# Cube4Control.net
KiCad netlist of a schematic drawn in EAGLE
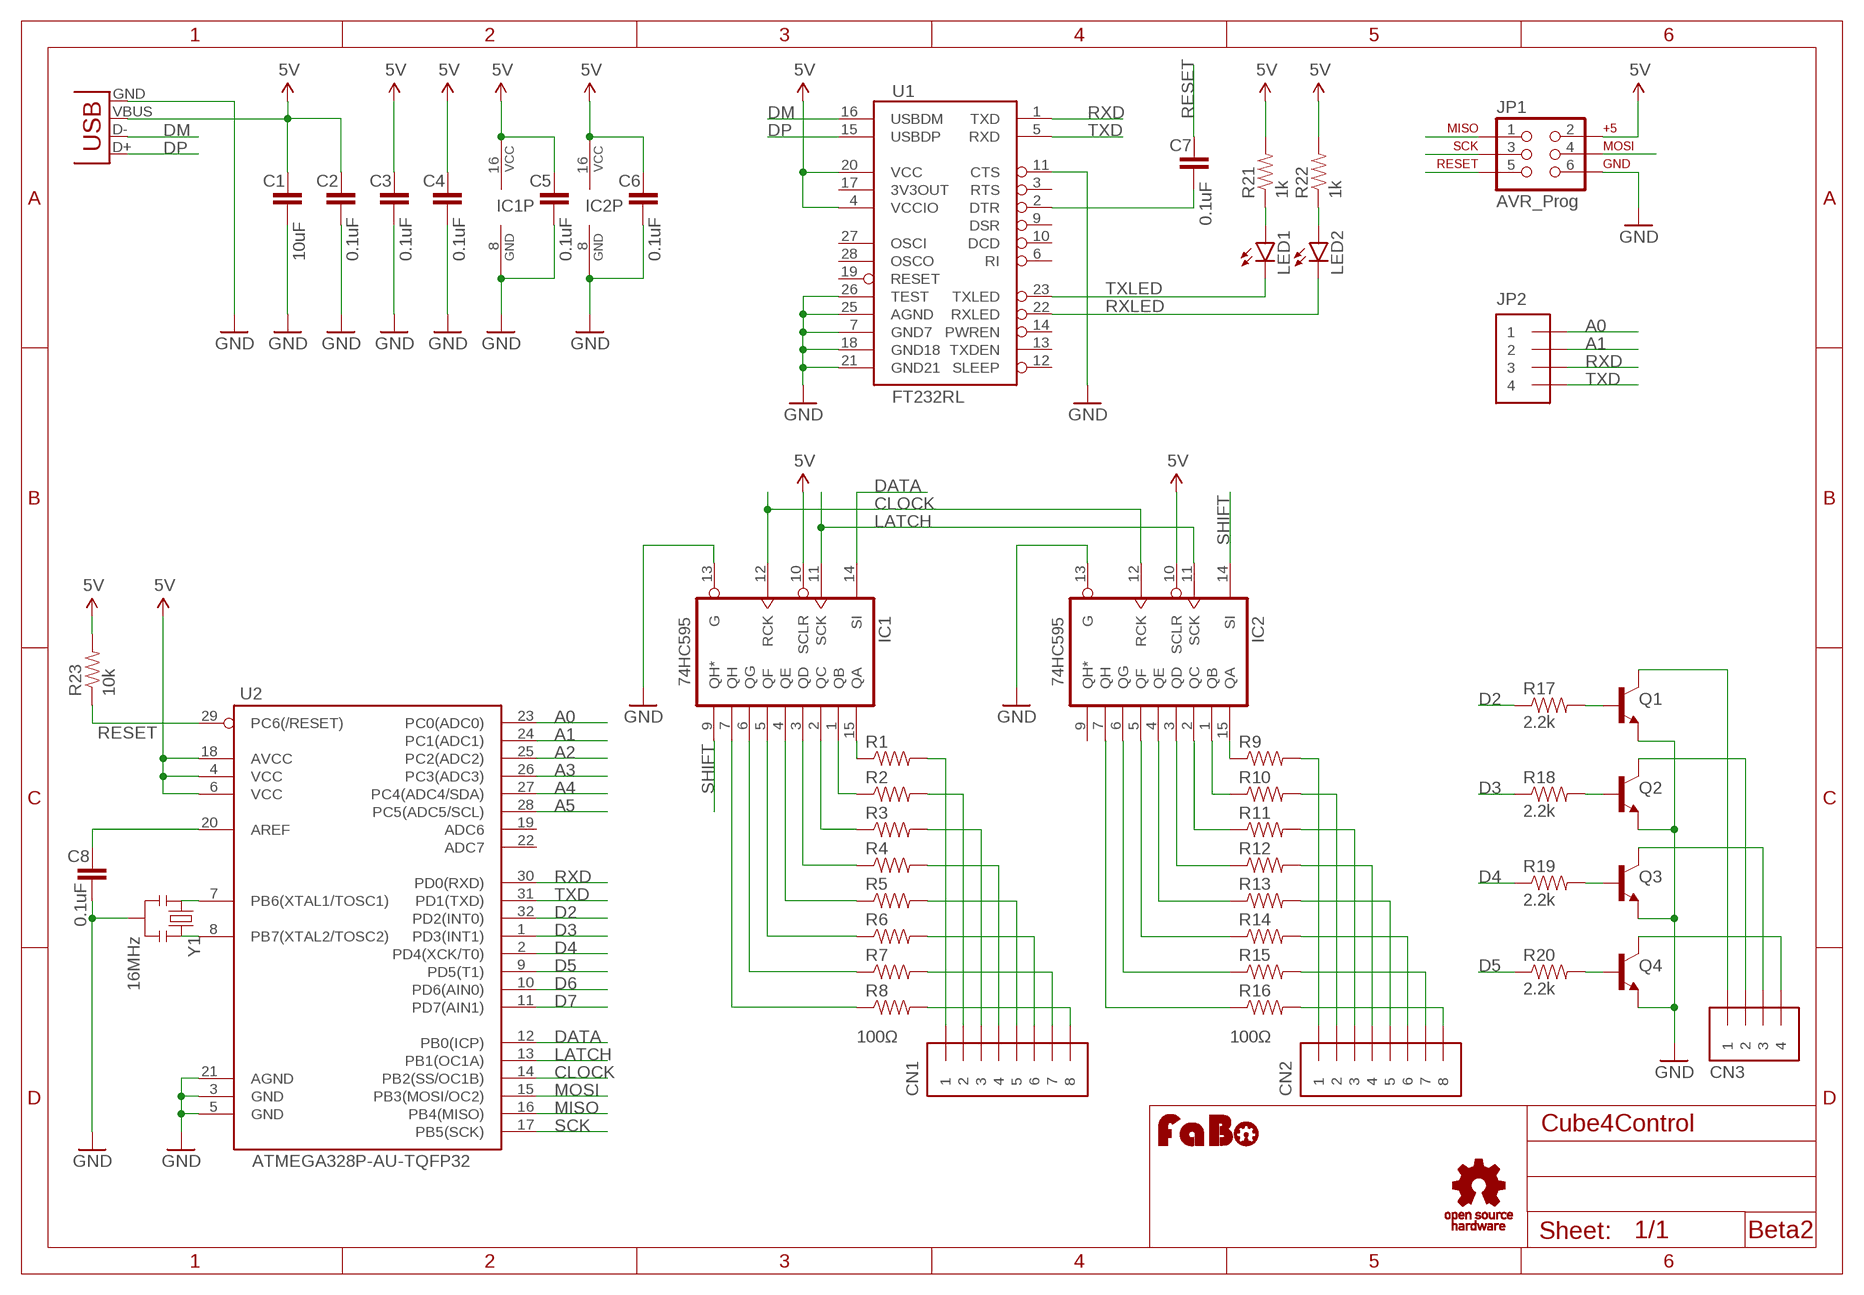
[diagram p0: schematic, sheet 1]

(export (version "E")
  (design (tool "Eeschema 10.0.6"))
  (components
    (comp (ref "C1")
      (value "10uF")
      (footprint "eagle-import:EIA1206")
      (libsource (lib "eagle-import") (part "CAP-EIA1206"))
    )
    (comp (ref "C2")
      (value "0.1uF")
      (footprint "eagle-import:EIA0603")
      (libsource (lib "eagle-import") (part "CAP-EIA0603"))
    )
    (comp (ref "C3")
      (value "0.1uF")
      (footprint "eagle-import:EIA0603")
      (libsource (lib "eagle-import") (part "CAP-EIA0603"))
    )
    (comp (ref "C4")
      (value "0.1uF")
      (footprint "eagle-import:EIA0603")
      (libsource (lib "eagle-import") (part "CAP-EIA0603"))
    )
    (comp (ref "C5")
      (value "0.1uF")
      (footprint "eagle-import:EIA0603")
      (libsource (lib "eagle-import") (part "CAP-EIA0603"))
    )
    (comp (ref "C6")
      (value "0.1uF")
      (footprint "eagle-import:EIA0603")
      (libsource (lib "eagle-import") (part "CAP-EIA0603"))
    )
    (comp (ref "C7")
      (value "0.1uF")
      (footprint "eagle-import:EIA0603")
      (libsource (lib "eagle-import") (part "CAP-EIA0603"))
    )
    (comp (ref "C8")
      (value "0.1uF")
      (footprint "eagle-import:EIA0603")
      (libsource (lib "eagle-import") (part "CAP-EIA0603"))
    )
    (comp (ref "CN1")
      (value "PINHEAD-1X8")
      (footprint "eagle-import:1X8-SNEAKY")
      (libsource (lib "eagle-import") (part "PINHEAD-1X8"))
    )
    (comp (ref "CN2")
      (value "PINHEAD-1X8")
      (footprint "eagle-import:1X8-SNEAKY")
      (libsource (lib "eagle-import") (part "PINHEAD-1X8"))
    )
    (comp (ref "CN3")
      (value "PINHEAD-1X4")
      (footprint "eagle-import:1X4-SNEAKY")
      (libsource (lib "eagle-import") (part "PINHEAD-1X4"))
    )
    (comp (ref "IC1")
      (value "74HC595")
      (footprint "eagle-import:SO16-3.9")
      (libsource (lib "eagle-import") (part "74HC595-SO16"))
    )
    (comp (ref "IC2")
      (value "74HC595")
      (footprint "eagle-import:SO16-3.9")
      (libsource (lib "eagle-import") (part "74HC595-SO16"))
    )
    (comp (ref "JP1")
      (value "AVR_Prog")
      (footprint "eagle-import:TC2030-MCP")
      (libsource (lib "eagle-import") (part "AVR_ISP-TC"))
    )
    (comp (ref "JP2")
      (value "PINHEAD-1X4")
      (footprint "eagle-import:1X4-SNEAKY")
      (libsource (lib "eagle-import") (part "PINHEAD-1X4"))
    )
    (comp (ref "LED1")
      (value "LED-EIA0603")
      (footprint "eagle-import:EIA0603-LED")
      (libsource (lib "eagle-import") (part "LED-EIA0603"))
    )
    (comp (ref "LED2")
      (value "LED-EIA0603")
      (footprint "eagle-import:EIA0603-LED")
      (libsource (lib "eagle-import") (part "LED-EIA0603"))
    )
    (comp (ref "Q1")
      (value "NPN-2SC3325")
      (footprint "eagle-import:SOT23-3")
      (libsource (lib "eagle-import") (part "NPN-2SC3325"))
    )
    (comp (ref "Q2")
      (value "NPN-2SC3325")
      (footprint "eagle-import:SOT23-3")
      (libsource (lib "eagle-import") (part "NPN-2SC3325"))
    )
    (comp (ref "Q3")
      (value "NPN-2SC3325")
      (footprint "eagle-import:SOT23-3")
      (libsource (lib "eagle-import") (part "NPN-2SC3325"))
    )
    (comp (ref "Q4")
      (value "NPN-2SC3325")
      (footprint "eagle-import:SOT23-3")
      (libsource (lib "eagle-import") (part "NPN-2SC3325"))
    )
    (comp (ref "R1")
      (value "RES-EIA0603")
      (footprint "eagle-import:EIA0603@1")
      (libsource (lib "eagle-import") (part "RES-EIA0603"))
    )
    (comp (ref "R2")
      (value "RES-EIA0603")
      (footprint "eagle-import:EIA0603@1")
      (libsource (lib "eagle-import") (part "RES-EIA0603"))
    )
    (comp (ref "R3")
      (value "RES-EIA0603")
      (footprint "eagle-import:EIA0603@1")
      (libsource (lib "eagle-import") (part "RES-EIA0603"))
    )
    (comp (ref "R4")
      (value "RES-EIA0603")
      (footprint "eagle-import:EIA0603@1")
      (libsource (lib "eagle-import") (part "RES-EIA0603"))
    )
    (comp (ref "R5")
      (value "RES-EIA0603")
      (footprint "eagle-import:EIA0603@1")
      (libsource (lib "eagle-import") (part "RES-EIA0603"))
    )
    (comp (ref "R6")
      (value "RES-EIA0603")
      (footprint "eagle-import:EIA0603@1")
      (libsource (lib "eagle-import") (part "RES-EIA0603"))
    )
    (comp (ref "R7")
      (value "RES-EIA0603")
      (footprint "eagle-import:EIA0603@1")
      (libsource (lib "eagle-import") (part "RES-EIA0603"))
    )
    (comp (ref "R8")
      (value "RES-EIA0603")
      (footprint "eagle-import:EIA0603@1")
      (libsource (lib "eagle-import") (part "RES-EIA0603"))
    )
    (comp (ref "R9")
      (value "RES-EIA0603")
      (footprint "eagle-import:EIA0603@1")
      (libsource (lib "eagle-import") (part "RES-EIA0603"))
    )
    (comp (ref "R10")
      (value "RES-EIA0603")
      (footprint "eagle-import:EIA0603@1")
      (libsource (lib "eagle-import") (part "RES-EIA0603"))
    )
    (comp (ref "R11")
      (value "RES-EIA0603")
      (footprint "eagle-import:EIA0603@1")
      (libsource (lib "eagle-import") (part "RES-EIA0603"))
    )
    (comp (ref "R12")
      (value "RES-EIA0603")
      (footprint "eagle-import:EIA0603@1")
      (libsource (lib "eagle-import") (part "RES-EIA0603"))
    )
    (comp (ref "R13")
      (value "RES-EIA0603")
      (footprint "eagle-import:EIA0603@1")
      (libsource (lib "eagle-import") (part "RES-EIA0603"))
    )
    (comp (ref "R14")
      (value "RES-EIA0603")
      (footprint "eagle-import:EIA0603@1")
      (libsource (lib "eagle-import") (part "RES-EIA0603"))
    )
    (comp (ref "R15")
      (value "RES-EIA0603")
      (footprint "eagle-import:EIA0603@1")
      (libsource (lib "eagle-import") (part "RES-EIA0603"))
    )
    (comp (ref "R16")
      (value "RES-EIA0603")
      (footprint "eagle-import:EIA0603@1")
      (libsource (lib "eagle-import") (part "RES-EIA0603"))
    )
    (comp (ref "R17")
      (value "2.2k")
      (footprint "eagle-import:EIA0603@1")
      (libsource (lib "eagle-import") (part "RES-EIA0603"))
    )
    (comp (ref "R18")
      (value "2.2k")
      (footprint "eagle-import:EIA0603@1")
      (libsource (lib "eagle-import") (part "RES-EIA0603"))
    )
    (comp (ref "R19")
      (value "2.2k")
      (footprint "eagle-import:EIA0603@1")
      (libsource (lib "eagle-import") (part "RES-EIA0603"))
    )
    (comp (ref "R20")
      (value "2.2k")
      (footprint "eagle-import:EIA0603@1")
      (libsource (lib "eagle-import") (part "RES-EIA0603"))
    )
    (comp (ref "R21")
      (value "1k")
      (footprint "eagle-import:EIA0603@1")
      (libsource (lib "eagle-import") (part "RES-EIA0603"))
    )
    (comp (ref "R22")
      (value "1k")
      (footprint "eagle-import:EIA0603@1")
      (libsource (lib "eagle-import") (part "RES-EIA0603"))
    )
    (comp (ref "R23")
      (value "10k")
      (footprint "eagle-import:EIA0603@1")
      (libsource (lib "eagle-import") (part "RES-EIA0603"))
    )
    (comp (ref "U$2")
      (value "LOGO_FABO-M")
      (footprint "eagle-import:LOGO_FABO_M")
      (libsource (lib "eagle-import") (part "LOGO_FABO-M"))
    )
    (comp (ref "U$4")
      (value "LOGO_OSHW_T-M")
      (footprint "eagle-import:LOGO_OSHW_T_M")
      (libsource (lib "eagle-import") (part "LOGO_OSHW_T-M"))
    )
    (comp (ref "U1")
      (value "FT232RL")
      (footprint "eagle-import:SSOP28")
      (libsource (lib "eagle-import") (part "FT232RL"))
    )
    (comp (ref "U2")
      (value "ATMEGA328P-AU-TQFP32")
      (footprint "eagle-import:TQFP-32-08")
      (libsource (lib "eagle-import") (part "ATMEGA328P-AU-TQFP32"))
    )
    (comp (ref "USB1")
      (value "USB-B-MICRO_SMD")
      (footprint "eagle-import:USB_B_MICRO")
      (libsource (lib "eagle-import") (part "USB-B-MICRO_SMD"))
    )
    (comp (ref "Y1")
      (value "16MHz")
      (footprint "eagle-import:RESONATOR_SMD")
      (libsource (lib "eagle-import") (part "RESONATOR"))
    )
  )
  (nets
    (net (code "1") (name "/A0") (class "Default")
      (node (ref "JP2") (pin "1") (pinfunction "1_1") (pintype "bidirectional"))
      (node (ref "U2") (pin "23") (pinfunction "PC0(ADC0)_23") (pintype "bidirectional"))
    )
    (net (code "2") (name "/A1") (class "Default")
      (node (ref "JP2") (pin "2") (pinfunction "2_2") (pintype "bidirectional"))
      (node (ref "U2") (pin "24") (pinfunction "PC1(ADC1)_24") (pintype "bidirectional"))
    )
    (net (code "3") (name "/A2") (class "Default")
      (node (ref "U2") (pin "25") (pinfunction "PC2(ADC2)_25") (pintype "bidirectional"))
    )
    (net (code "4") (name "/A3") (class "Default")
      (node (ref "U2") (pin "26") (pinfunction "PC3(ADC3)_26") (pintype "bidirectional"))
    )
    (net (code "5") (name "/A4") (class "Default")
      (node (ref "U2") (pin "27") (pinfunction "PC4(ADC4/SDA)_27") (pintype "bidirectional"))
    )
    (net (code "6") (name "/A5") (class "Default")
      (node (ref "U2") (pin "28") (pinfunction "PC5(ADC5/SCL)_28") (pintype "bidirectional"))
    )
    (net (code "7") (name "/CLOCK") (class "Default")
      (node (ref "IC1") (pin "12") (pinfunction "RCK_12") (pintype "input"))
      (node (ref "IC2") (pin "12") (pinfunction "RCK_12") (pintype "input"))
      (node (ref "U2") (pin "14") (pinfunction "PB2(SS/OC1B)_14") (pintype "bidirectional"))
    )
    (net (code "8") (name "/D2") (class "Default")
      (node (ref "R17") (pin "1") (pinfunction "1_1") (pintype "passive"))
      (node (ref "U2") (pin "32") (pinfunction "PD2(INT0)_32") (pintype "bidirectional"))
    )
    (net (code "9") (name "/D3") (class "Default")
      (node (ref "R18") (pin "1") (pinfunction "1_1") (pintype "passive"))
      (node (ref "U2") (pin "1") (pinfunction "PD3(INT1)_1") (pintype "bidirectional"))
    )
    (net (code "10") (name "/D4") (class "Default")
      (node (ref "R19") (pin "1") (pinfunction "1_1") (pintype "passive"))
      (node (ref "U2") (pin "2") (pinfunction "PD4(XCK/T0)_2") (pintype "bidirectional"))
    )
    (net (code "11") (name "/D5") (class "Default")
      (node (ref "R20") (pin "1") (pinfunction "1_1") (pintype "passive"))
      (node (ref "U2") (pin "9") (pinfunction "PD5(T1)_9") (pintype "bidirectional"))
    )
    (net (code "12") (name "/D6") (class "Default")
      (node (ref "U2") (pin "10") (pinfunction "PD6(AIN0)_10") (pintype "bidirectional"))
    )
    (net (code "13") (name "/D7") (class "Default")
      (node (ref "U2") (pin "11") (pinfunction "PD7(AIN1)_11") (pintype "bidirectional"))
    )
    (net (code "14") (name "/DATA") (class "Default")
      (node (ref "IC1") (pin "14") (pinfunction "SI_14") (pintype "input"))
      (node (ref "U2") (pin "12") (pinfunction "PB0(ICP)_12") (pintype "bidirectional"))
    )
    (net (code "15") (name "/DM") (class "Default")
      (node (ref "U1") (pin "16") (pinfunction "USBDM_16") (pintype "bidirectional"))
      (node (ref "USB1") (pin "D-") (pinfunction "D-_D-") (pintype "bidirectional"))
    )
    (net (code "16") (name "/DP") (class "Default")
      (node (ref "U1") (pin "15") (pinfunction "USBDP_15") (pintype "bidirectional"))
      (node (ref "USB1") (pin "D+") (pinfunction "D+_D+") (pintype "bidirectional"))
    )
    (net (code "17") (name "/LATCH") (class "Default")
      (node (ref "IC1") (pin "11") (pinfunction "SCK_11") (pintype "input"))
      (node (ref "IC2") (pin "11") (pinfunction "SCK_11") (pintype "input"))
      (node (ref "U2") (pin "13") (pinfunction "PB1(OC1A)_13") (pintype "bidirectional"))
    )
    (net (code "18") (name "/MISO") (class "Default")
      (node (ref "JP1") (pin "1") (pinfunction "1_1") (pintype "passive"))
      (node (ref "U2") (pin "16") (pinfunction "PB4(MISO)_16") (pintype "bidirectional"))
    )
    (net (code "19") (name "/MOSI") (class "Default")
      (node (ref "JP1") (pin "4") (pinfunction "4_4") (pintype "passive"))
      (node (ref "U2") (pin "15") (pinfunction "PB3(MOSI/OC2)_15") (pintype "bidirectional"))
    )
    (net (code "20") (name "/RESET") (class "Default")
      (node (ref "C7") (pin "1") (pinfunction "1_1") (pintype "passive"))
      (node (ref "JP1") (pin "5") (pinfunction "5_5") (pintype "passive"))
      (node (ref "R23") (pin "1") (pinfunction "1_1") (pintype "passive"))
      (node (ref "U2") (pin "29") (pinfunction "PC6(/RESET)_29") (pintype "bidirectional"))
    )
    (net (code "21") (name "/RXD") (class "Default")
      (node (ref "JP2") (pin "3") (pinfunction "3_3") (pintype "bidirectional"))
      (node (ref "U1") (pin "1") (pinfunction "TXD_1") (pintype "output"))
      (node (ref "U2") (pin "30") (pinfunction "PD0(RXD)_30") (pintype "bidirectional"))
    )
    (net (code "22") (name "/RXLED") (class "Default")
      (node (ref "LED2") (pin "C") (pinfunction "C_C") (pintype "passive"))
      (node (ref "U1") (pin "22") (pinfunction "RXLED_22") (pintype "input"))
    )
    (net (code "23") (name "/SCK") (class "Default")
      (node (ref "JP1") (pin "3") (pinfunction "3_3") (pintype "passive"))
      (node (ref "U2") (pin "17") (pinfunction "PB5(SCK)_17") (pintype "bidirectional"))
    )
    (net (code "24") (name "/SHIFT") (class "Default")
      (node (ref "IC1") (pin "9") (pinfunction "QH*_9") (pintype "tri_state"))
      (node (ref "IC2") (pin "14") (pinfunction "SI_14") (pintype "input"))
    )
    (net (code "25") (name "/TXD") (class "Default")
      (node (ref "JP2") (pin "4") (pinfunction "4_4") (pintype "bidirectional"))
      (node (ref "U1") (pin "5") (pinfunction "RXD_5") (pintype "input"))
      (node (ref "U2") (pin "31") (pinfunction "PD1(TXD)_31") (pintype "bidirectional"))
    )
    (net (code "26") (name "/TXLED") (class "Default")
      (node (ref "LED1") (pin "C") (pinfunction "C_C") (pintype "passive"))
      (node (ref "U1") (pin "23") (pinfunction "TXLED_23") (pintype "input"))
    )
    (net (code "27") (name "5V") (class "Default")
      (node (ref "C1") (pin "1") (pinfunction "1_1") (pintype "passive"))
      (node (ref "C2") (pin "1") (pinfunction "1_1") (pintype "passive"))
      (node (ref "C3") (pin "1") (pinfunction "1_1") (pintype "passive"))
      (node (ref "C4") (pin "1") (pinfunction "1_1") (pintype "passive"))
      (node (ref "C5") (pin "1") (pinfunction "1_1") (pintype "passive"))
      (node (ref "C6") (pin "1") (pinfunction "1_1") (pintype "passive"))
      (node (ref "IC1") (pin "10") (pinfunction "SCLR_10") (pintype "input"))
      (node (ref "IC1") (pin "16") (pinfunction "VCC_16") (pintype "power_in"))
      (node (ref "IC2") (pin "10") (pinfunction "SCLR_10") (pintype "input"))
      (node (ref "IC2") (pin "16") (pinfunction "VCC_16") (pintype "power_in"))
      (node (ref "JP1") (pin "2") (pinfunction "2_2") (pintype "passive"))
      (node (ref "R21") (pin "2") (pinfunction "2_2") (pintype "passive"))
      (node (ref "R22") (pin "2") (pinfunction "2_2") (pintype "passive"))
      (node (ref "R23") (pin "2") (pinfunction "2_2") (pintype "passive"))
      (node (ref "U1") (pin "20") (pinfunction "VCC_20") (pintype "power_in"))
      (node (ref "U1") (pin "4") (pinfunction "VCCIO_4") (pintype "power_in"))
      (node (ref "U2") (pin "18") (pinfunction "AVCC_18") (pintype "bidirectional"))
      (node (ref "U2") (pin "4") (pinfunction "VCC_4") (pintype "bidirectional"))
      (node (ref "U2") (pin "6") (pinfunction "VCC_6") (pintype "bidirectional"))
      (node (ref "USB1") (pin "VBUS") (pinfunction "VBUS_VBUS") (pintype "bidirectional"))
    )
    (net (code "28") (name "GND") (class "Default")
      (node (ref "C1") (pin "2") (pinfunction "2_2") (pintype "passive"))
      (node (ref "C2") (pin "2") (pinfunction "2_2") (pintype "passive"))
      (node (ref "C3") (pin "2") (pinfunction "2_2") (pintype "passive"))
      (node (ref "C4") (pin "2") (pinfunction "2_2") (pintype "passive"))
      (node (ref "C5") (pin "2") (pinfunction "2_2") (pintype "passive"))
      (node (ref "C6") (pin "2") (pinfunction "2_2") (pintype "passive"))
      (node (ref "C8") (pin "2") (pinfunction "2_2") (pintype "passive"))
      (node (ref "IC1") (pin "13") (pinfunction "G_13") (pintype "input"))
      (node (ref "IC1") (pin "8") (pinfunction "GND_8") (pintype "power_in"))
      (node (ref "IC2") (pin "13") (pinfunction "G_13") (pintype "input"))
      (node (ref "IC2") (pin "8") (pinfunction "GND_8") (pintype "power_in"))
      (node (ref "JP1") (pin "6") (pinfunction "6_6") (pintype "passive"))
      (node (ref "Q1") (pin "2") (pinfunction "E_2") (pintype "passive"))
      (node (ref "Q2") (pin "2") (pinfunction "E_2") (pintype "passive"))
      (node (ref "Q3") (pin "2") (pinfunction "E_2") (pintype "passive"))
      (node (ref "Q4") (pin "2") (pinfunction "E_2") (pintype "passive"))
      (node (ref "U1") (pin "11") (pinfunction "CTS_11") (pintype "input"))
      (node (ref "U1") (pin "18") (pinfunction "GND18_18") (pintype "power_in"))
      (node (ref "U1") (pin "21") (pinfunction "GND21_21") (pintype "power_in"))
      (node (ref "U1") (pin "25") (pinfunction "AGND_25") (pintype "power_in"))
      (node (ref "U1") (pin "26") (pinfunction "TEST_26") (pintype "input"))
      (node (ref "U1") (pin "7") (pinfunction "GND7_7") (pintype "power_in"))
      (node (ref "U2") (pin "21") (pinfunction "AGND_21") (pintype "bidirectional"))
      (node (ref "U2") (pin "3") (pinfunction "GND_3") (pintype "bidirectional"))
      (node (ref "U2") (pin "5") (pinfunction "GND_5") (pintype "bidirectional"))
      (node (ref "USB1") (pin "GND") (pinfunction "GND_GND") (pintype "bidirectional"))
      (node (ref "Y1") (pin "2") (pinfunction "2_2") (pintype "passive"))
    )
    (net (code "29") (name "Net-(CN1-Pad1)") (class "Default")
      (node (ref "CN1") (pin "1") (pinfunction "1_1") (pintype "bidirectional"))
      (node (ref "R1") (pin "2") (pinfunction "2_2") (pintype "passive"))
    )
    (net (code "30") (name "Net-(CN1-Pad2)") (class "Default")
      (node (ref "CN1") (pin "2") (pinfunction "2_2") (pintype "bidirectional"))
      (node (ref "R2") (pin "2") (pinfunction "2_2") (pintype "passive"))
    )
    (net (code "31") (name "Net-(CN1-Pad3)") (class "Default")
      (node (ref "CN1") (pin "3") (pinfunction "3_3") (pintype "bidirectional"))
      (node (ref "R3") (pin "2") (pinfunction "2_2") (pintype "passive"))
    )
    (net (code "32") (name "Net-(CN1-Pad4)") (class "Default")
      (node (ref "CN1") (pin "4") (pinfunction "4_4") (pintype "bidirectional"))
      (node (ref "R4") (pin "2") (pinfunction "2_2") (pintype "passive"))
    )
    (net (code "33") (name "Net-(CN1-Pad5)") (class "Default")
      (node (ref "CN1") (pin "5") (pinfunction "5_5") (pintype "bidirectional"))
      (node (ref "R5") (pin "2") (pinfunction "2_2") (pintype "passive"))
    )
    (net (code "34") (name "Net-(CN1-Pad6)") (class "Default")
      (node (ref "CN1") (pin "6") (pinfunction "6_6") (pintype "bidirectional"))
      (node (ref "R6") (pin "2") (pinfunction "2_2") (pintype "passive"))
    )
    (net (code "35") (name "Net-(CN1-Pad7)") (class "Default")
      (node (ref "CN1") (pin "7") (pinfunction "7_7") (pintype "bidirectional"))
      (node (ref "R7") (pin "2") (pinfunction "2_2") (pintype "passive"))
    )
    (net (code "36") (name "Net-(CN1-Pad8)") (class "Default")
      (node (ref "CN1") (pin "8") (pinfunction "8_8") (pintype "bidirectional"))
      (node (ref "R8") (pin "2") (pinfunction "2_2") (pintype "passive"))
    )
    (net (code "37") (name "Net-(CN2-Pad1)") (class "Default")
      (node (ref "CN2") (pin "1") (pinfunction "1_1") (pintype "bidirectional"))
      (node (ref "R9") (pin "2") (pinfunction "2_2") (pintype "passive"))
    )
    (net (code "38") (name "Net-(CN2-Pad2)") (class "Default")
      (node (ref "CN2") (pin "2") (pinfunction "2_2") (pintype "bidirectional"))
      (node (ref "R10") (pin "2") (pinfunction "2_2") (pintype "passive"))
    )
    (net (code "39") (name "Net-(CN2-Pad3)") (class "Default")
      (node (ref "CN2") (pin "3") (pinfunction "3_3") (pintype "bidirectional"))
      (node (ref "R11") (pin "2") (pinfunction "2_2") (pintype "passive"))
    )
    (net (code "40") (name "Net-(CN2-Pad4)") (class "Default")
      (node (ref "CN2") (pin "4") (pinfunction "4_4") (pintype "bidirectional"))
      (node (ref "R12") (pin "2") (pinfunction "2_2") (pintype "passive"))
    )
    (net (code "41") (name "Net-(CN2-Pad5)") (class "Default")
      (node (ref "CN2") (pin "5") (pinfunction "5_5") (pintype "bidirectional"))
      (node (ref "R13") (pin "2") (pinfunction "2_2") (pintype "passive"))
    )
    (net (code "42") (name "Net-(CN2-Pad6)") (class "Default")
      (node (ref "CN2") (pin "6") (pinfunction "6_6") (pintype "bidirectional"))
      (node (ref "R14") (pin "2") (pinfunction "2_2") (pintype "passive"))
    )
    (net (code "43") (name "Net-(CN2-Pad7)") (class "Default")
      (node (ref "CN2") (pin "7") (pinfunction "7_7") (pintype "bidirectional"))
      (node (ref "R15") (pin "2") (pinfunction "2_2") (pintype "passive"))
    )
    (net (code "44") (name "Net-(CN2-Pad8)") (class "Default")
      (node (ref "CN2") (pin "8") (pinfunction "8_8") (pintype "bidirectional"))
      (node (ref "R16") (pin "2") (pinfunction "2_2") (pintype "passive"))
    )
    (net (code "45") (name "Net-(IC1A-QA)") (class "Default")
      (node (ref "IC1") (pin "15") (pinfunction "QA_15") (pintype "tri_state"))
      (node (ref "R1") (pin "1") (pinfunction "1_1") (pintype "passive"))
    )
    (net (code "46") (name "Net-(IC1A-QB)") (class "Default")
      (node (ref "IC1") (pin "1") (pinfunction "QB_1") (pintype "tri_state"))
      (node (ref "R2") (pin "1") (pinfunction "1_1") (pintype "passive"))
    )
    (net (code "47") (name "Net-(IC1A-QC)") (class "Default")
      (node (ref "IC1") (pin "2") (pinfunction "QC_2") (pintype "tri_state"))
      (node (ref "R3") (pin "1") (pinfunction "1_1") (pintype "passive"))
    )
    (net (code "48") (name "Net-(IC1A-QD)") (class "Default")
      (node (ref "IC1") (pin "3") (pinfunction "QD_3") (pintype "tri_state"))
      (node (ref "R4") (pin "1") (pinfunction "1_1") (pintype "passive"))
    )
    (net (code "49") (name "Net-(IC1A-QE)") (class "Default")
      (node (ref "IC1") (pin "4") (pinfunction "QE_4") (pintype "tri_state"))
      (node (ref "R5") (pin "1") (pinfunction "1_1") (pintype "passive"))
    )
    (net (code "50") (name "Net-(IC1A-QF)") (class "Default")
      (node (ref "IC1") (pin "5") (pinfunction "QF_5") (pintype "tri_state"))
      (node (ref "R6") (pin "1") (pinfunction "1_1") (pintype "passive"))
    )
    (net (code "51") (name "Net-(IC1A-QG)") (class "Default")
      (node (ref "IC1") (pin "6") (pinfunction "QG_6") (pintype "tri_state"))
      (node (ref "R7") (pin "1") (pinfunction "1_1") (pintype "passive"))
    )
    (net (code "52") (name "Net-(IC1A-QH)") (class "Default")
      (node (ref "IC1") (pin "7") (pinfunction "QH_7") (pintype "tri_state"))
      (node (ref "R8") (pin "1") (pinfunction "1_1") (pintype "passive"))
    )
    (net (code "53") (name "Net-(IC2A-QA)") (class "Default")
      (node (ref "IC2") (pin "15") (pinfunction "QA_15") (pintype "tri_state"))
      (node (ref "R9") (pin "1") (pinfunction "1_1") (pintype "passive"))
    )
    (net (code "54") (name "Net-(IC2A-QB)") (class "Default")
      (node (ref "IC2") (pin "1") (pinfunction "QB_1") (pintype "tri_state"))
      (node (ref "R10") (pin "1") (pinfunction "1_1") (pintype "passive"))
    )
    (net (code "55") (name "Net-(IC2A-QC)") (class "Default")
      (node (ref "IC2") (pin "2") (pinfunction "QC_2") (pintype "tri_state"))
      (node (ref "R11") (pin "1") (pinfunction "1_1") (pintype "passive"))
    )
    (net (code "56") (name "Net-(IC2A-QD)") (class "Default")
      (node (ref "IC2") (pin "3") (pinfunction "QD_3") (pintype "tri_state"))
      (node (ref "R12") (pin "1") (pinfunction "1_1") (pintype "passive"))
    )
    (net (code "57") (name "Net-(IC2A-QE)") (class "Default")
      (node (ref "IC2") (pin "4") (pinfunction "QE_4") (pintype "tri_state"))
      (node (ref "R13") (pin "1") (pinfunction "1_1") (pintype "passive"))
    )
    (net (code "58") (name "Net-(IC2A-QF)") (class "Default")
      (node (ref "IC2") (pin "5") (pinfunction "QF_5") (pintype "tri_state"))
      (node (ref "R14") (pin "1") (pinfunction "1_1") (pintype "passive"))
    )
    (net (code "59") (name "Net-(IC2A-QG)") (class "Default")
      (node (ref "IC2") (pin "6") (pinfunction "QG_6") (pintype "tri_state"))
      (node (ref "R15") (pin "1") (pinfunction "1_1") (pintype "passive"))
    )
    (net (code "60") (name "Net-(IC2A-QH)") (class "Default")
      (node (ref "IC2") (pin "7") (pinfunction "QH_7") (pintype "tri_state"))
      (node (ref "R16") (pin "1") (pinfunction "1_1") (pintype "passive"))
    )
    (net (code "61") (name "Net-(LED1-PadA)") (class "Default")
      (node (ref "LED1") (pin "A") (pinfunction "A_A") (pintype "passive"))
      (node (ref "R21") (pin "1") (pinfunction "1_1") (pintype "passive"))
    )
    (net (code "62") (name "Net-(LED2-PadA)") (class "Default")
      (node (ref "LED2") (pin "A") (pinfunction "A_A") (pintype "passive"))
      (node (ref "R22") (pin "1") (pinfunction "1_1") (pintype "passive"))
    )
    (net (code "63") (name "Net-(Q1-B)") (class "Default")
      (node (ref "Q1") (pin "1") (pinfunction "B_1") (pintype "passive"))
      (node (ref "R17") (pin "2") (pinfunction "2_2") (pintype "passive"))
    )
    (net (code "64") (name "Net-(Q1-C)") (class "Default")
      (node (ref "CN3") (pin "1") (pinfunction "1_1") (pintype "bidirectional"))
      (node (ref "Q1") (pin "3") (pinfunction "C_3") (pintype "passive"))
    )
    (net (code "65") (name "Net-(Q2-B)") (class "Default")
      (node (ref "Q2") (pin "1") (pinfunction "B_1") (pintype "passive"))
      (node (ref "R18") (pin "2") (pinfunction "2_2") (pintype "passive"))
    )
    (net (code "66") (name "Net-(Q2-C)") (class "Default")
      (node (ref "CN3") (pin "2") (pinfunction "2_2") (pintype "bidirectional"))
      (node (ref "Q2") (pin "3") (pinfunction "C_3") (pintype "passive"))
    )
    (net (code "67") (name "Net-(Q3-B)") (class "Default")
      (node (ref "Q3") (pin "1") (pinfunction "B_1") (pintype "passive"))
      (node (ref "R19") (pin "2") (pinfunction "2_2") (pintype "passive"))
    )
    (net (code "68") (name "Net-(Q3-C)") (class "Default")
      (node (ref "CN3") (pin "3") (pinfunction "3_3") (pintype "bidirectional"))
      (node (ref "Q3") (pin "3") (pinfunction "C_3") (pintype "passive"))
    )
    (net (code "69") (name "Net-(Q4-B)") (class "Default")
      (node (ref "Q4") (pin "1") (pinfunction "B_1") (pintype "passive"))
      (node (ref "R20") (pin "2") (pinfunction "2_2") (pintype "passive"))
    )
    (net (code "70") (name "Net-(Q4-C)") (class "Default")
      (node (ref "CN3") (pin "4") (pinfunction "4_4") (pintype "bidirectional"))
      (node (ref "Q4") (pin "3") (pinfunction "C_3") (pintype "passive"))
    )
    (net (code "71") (name "Net-(U1-DTR)") (class "Default")
      (node (ref "C7") (pin "2") (pinfunction "2_2") (pintype "passive"))
      (node (ref "U1") (pin "2") (pinfunction "DTR_2") (pintype "output"))
    )
    (net (code "72") (name "Net-(U2-AREF)") (class "Default")
      (node (ref "C8") (pin "1") (pinfunction "1_1") (pintype "passive"))
      (node (ref "U2") (pin "20") (pinfunction "AREF_20") (pintype "bidirectional"))
    )
    (net (code "73") (name "Net-(U2-PB6(XTAL1{slash}TOSC1))") (class "Default")
      (node (ref "U2") (pin "7") (pinfunction "PB6(XTAL1/TOSC1)_7") (pintype "bidirectional"))
      (node (ref "Y1") (pin "1") (pinfunction "1_1") (pintype "passive"))
    )
    (net (code "74") (name "Net-(U2-PB7(XTAL2{slash}TOSC2))") (class "Default")
      (node (ref "U2") (pin "8") (pinfunction "PB7(XTAL2/TOSC2)_8") (pintype "bidirectional"))
      (node (ref "Y1") (pin "3") (pinfunction "3_3") (pintype "passive"))
    )
    (net (code "75") (name "unconnected-(IC2A-QH*-Pad9)") (class "Default")
      (node (ref "IC2") (pin "9") (pinfunction "QH*_9") (pintype "tri_state"))
    )
    (net (code "76") (name "unconnected-(U1-3V3OUT-Pad17)") (class "Default")
      (node (ref "U1") (pin "17") (pinfunction "3V3OUT_17") (pintype "output"))
    )
    (net (code "77") (name "unconnected-(U1-DCD-Pad10)") (class "Default")
      (node (ref "U1") (pin "10") (pinfunction "DCD_10") (pintype "input"))
    )
    (net (code "78") (name "unconnected-(U1-DSR-Pad9)") (class "Default")
      (node (ref "U1") (pin "9") (pinfunction "DSR_9") (pintype "input"))
    )
    (net (code "79") (name "unconnected-(U1-OSCI-Pad27)") (class "Default")
      (node (ref "U1") (pin "27") (pinfunction "OSCI_27") (pintype "input"))
    )
    (net (code "80") (name "unconnected-(U1-OSCO-Pad28)") (class "Default")
      (node (ref "U1") (pin "28") (pinfunction "OSCO_28") (pintype "output"))
    )
    (net (code "81") (name "unconnected-(U1-PWREN-Pad14)") (class "Default")
      (node (ref "U1") (pin "14") (pinfunction "PWREN_14") (pintype "input"))
    )
    (net (code "82") (name "unconnected-(U1-RESET-Pad19)") (class "Default")
      (node (ref "U1") (pin "19") (pinfunction "RESET_19") (pintype "input"))
    )
    (net (code "83") (name "unconnected-(U1-RI-Pad6)") (class "Default")
      (node (ref "U1") (pin "6") (pinfunction "RI_6") (pintype "input"))
    )
    (net (code "84") (name "unconnected-(U1-RTS-Pad3)") (class "Default")
      (node (ref "U1") (pin "3") (pinfunction "RTS_3") (pintype "output"))
    )
    (net (code "85") (name "unconnected-(U1-SLEEP-Pad12)") (class "Default")
      (node (ref "U1") (pin "12") (pinfunction "SLEEP_12") (pintype "input"))
    )
    (net (code "86") (name "unconnected-(U1-TXDEN-Pad13)") (class "Default")
      (node (ref "U1") (pin "13") (pinfunction "TXDEN_13") (pintype "input"))
    )
    (net (code "87") (name "unconnected-(U2-ADC6-Pad19)") (class "Default")
      (node (ref "U2") (pin "19") (pinfunction "ADC6_19") (pintype "bidirectional"))
    )
    (net (code "88") (name "unconnected-(U2-ADC7-Pad22)") (class "Default")
      (node (ref "U2") (pin "22") (pinfunction "ADC7_22") (pintype "bidirectional"))
    )
  )
)
